# LM399_reference_board.net
KiCad netlist of a schematic drawn in EAGLE
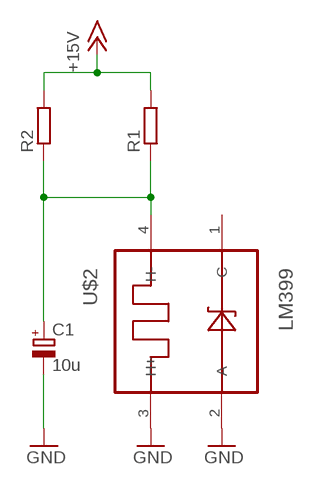
[diagram p0: schematic, sheet 1]

(export (version "E")
  (design (tool "Eeschema 10.0.6"))
  (components
    (comp (ref "C1")
      (value "10u")
      (footprint "eagle-import:SMC_D")
      (libsource (lib "eagle-import") (part "CPOL-EUSMCD"))
    )
    (comp (ref "R1")
      (value "R-EU_R1206")
      (footprint "eagle-import:R1206")
      (libsource (lib "eagle-import") (part "R-EU_R1206"))
    )
    (comp (ref "R2")
      (value "R-EU_0309/12")
      (footprint "eagle-import:0309_12")
      (libsource (lib "eagle-import") (part "R-EU_0309/12"))
    )
    (comp (ref "U$2")
      (value "LM399")
      (footprint "eagle-import:H4-TO46-4PIN")
      (libsource (lib "eagle-import") (part "LM399"))
    )
  )
  (nets
    (net (code "1") (name "+15V") (class "Default")
      (node (ref "R1") (pin "2") (pinfunction "2_2") (pintype "passive"))
      (node (ref "R2") (pin "2") (pinfunction "2_2") (pintype "passive"))
    )
    (net (code "2") (name "GND") (class "Default")
      (node (ref "C1") (pin "-") (pinfunction "-_-") (pintype "passive"))
      (node (ref "U$2") (pin "2") (pinfunction "A_2") (pintype "input"))
      (node (ref "U$2") (pin "3") (pinfunction "H+_3") (pintype "input"))
    )
    (net (code "3") (name "Net-(U$2-H-)") (class "Default")
      (node (ref "C1") (pin "+") (pinfunction "+_+") (pintype "passive"))
      (node (ref "R1") (pin "1") (pinfunction "1_1") (pintype "passive"))
      (node (ref "R2") (pin "1") (pinfunction "1_1") (pintype "passive"))
      (node (ref "U$2") (pin "4") (pinfunction "H-_4") (pintype "input"))
    )
    (net (code "4") (name "unconnected-(U$2-C-Pad1)") (class "Default")
      (node (ref "U$2") (pin "1") (pinfunction "C_1") (pintype "input"))
    )
  )
)
